# joystick.net
KiCad netlist of a schematic drawn in EAGLE
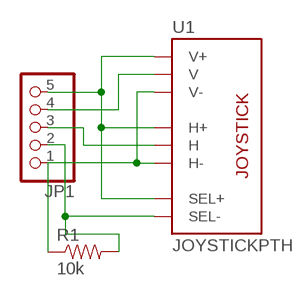
[diagram p0: schematic, sheet 1]

(export (version "E")
  (design (tool "Eeschema 10.0.6"))
  (components
    (comp (ref "JP1")
      (value "PINHD-1X5")
      (footprint "eagle-import:1X05")
      (libsource (lib "eagle-import") (part "PINHD-1X5"))
    )
    (comp (ref "R1")
      (value "10k")
      (footprint "eagle-import:0805")
      (libsource (lib "eagle-import") (part "RESISTOR0805-RES"))
    )
    (comp (ref "U1")
      (value "JOYSTICKPTH")
      (footprint "eagle-import:JOYSTICK")
      (libsource (lib "eagle-import") (part "JOYSTICKPTH"))
    )
  )
  (nets
    (net (code "1") (name "Net-(U1-H)") (class "Default")
      (node (ref "JP1") (pin "3") (pinfunction "3_3") (pintype "passive"))
      (node (ref "U1") (pin "H2") (pinfunction "H_H2") (pintype "bidirectional"))
    )
    (net (code "2") (name "Net-(U1-H+)") (class "Default")
      (node (ref "JP1") (pin "5") (pinfunction "5_5") (pintype "passive"))
      (node (ref "U1") (pin "B1A") (pinfunction "SEL+_B1A") (pintype "bidirectional"))
      (node (ref "U1") (pin "H1") (pinfunction "H+_H1") (pintype "bidirectional"))
      (node (ref "U1") (pin "V1") (pinfunction "V+_V1") (pintype "bidirectional"))
    )
    (net (code "3") (name "Net-(U1-H-)") (class "Default")
      (node (ref "JP1") (pin "1") (pinfunction "1_1") (pintype "passive"))
      (node (ref "R1") (pin "1") (pinfunction "1_1") (pintype "passive"))
      (node (ref "U1") (pin "H3") (pinfunction "H-_H3") (pintype "bidirectional"))
      (node (ref "U1") (pin "V3") (pinfunction "V-_V3") (pintype "bidirectional"))
    )
    (net (code "4") (name "Net-(U1-SEL-)") (class "Default")
      (node (ref "JP1") (pin "2") (pinfunction "2_2") (pintype "passive"))
      (node (ref "R1") (pin "2") (pinfunction "2_2") (pintype "passive"))
      (node (ref "U1") (pin "B2A") (pinfunction "SEL-_B2A") (pintype "bidirectional"))
    )
    (net (code "5") (name "Net-(U1-V)") (class "Default")
      (node (ref "JP1") (pin "4") (pinfunction "4_4") (pintype "passive"))
      (node (ref "U1") (pin "V2") (pinfunction "V_V2") (pintype "bidirectional"))
    )
  )
)
